# Display.net
KiCad netlist of a schematic drawn in Altium Designer
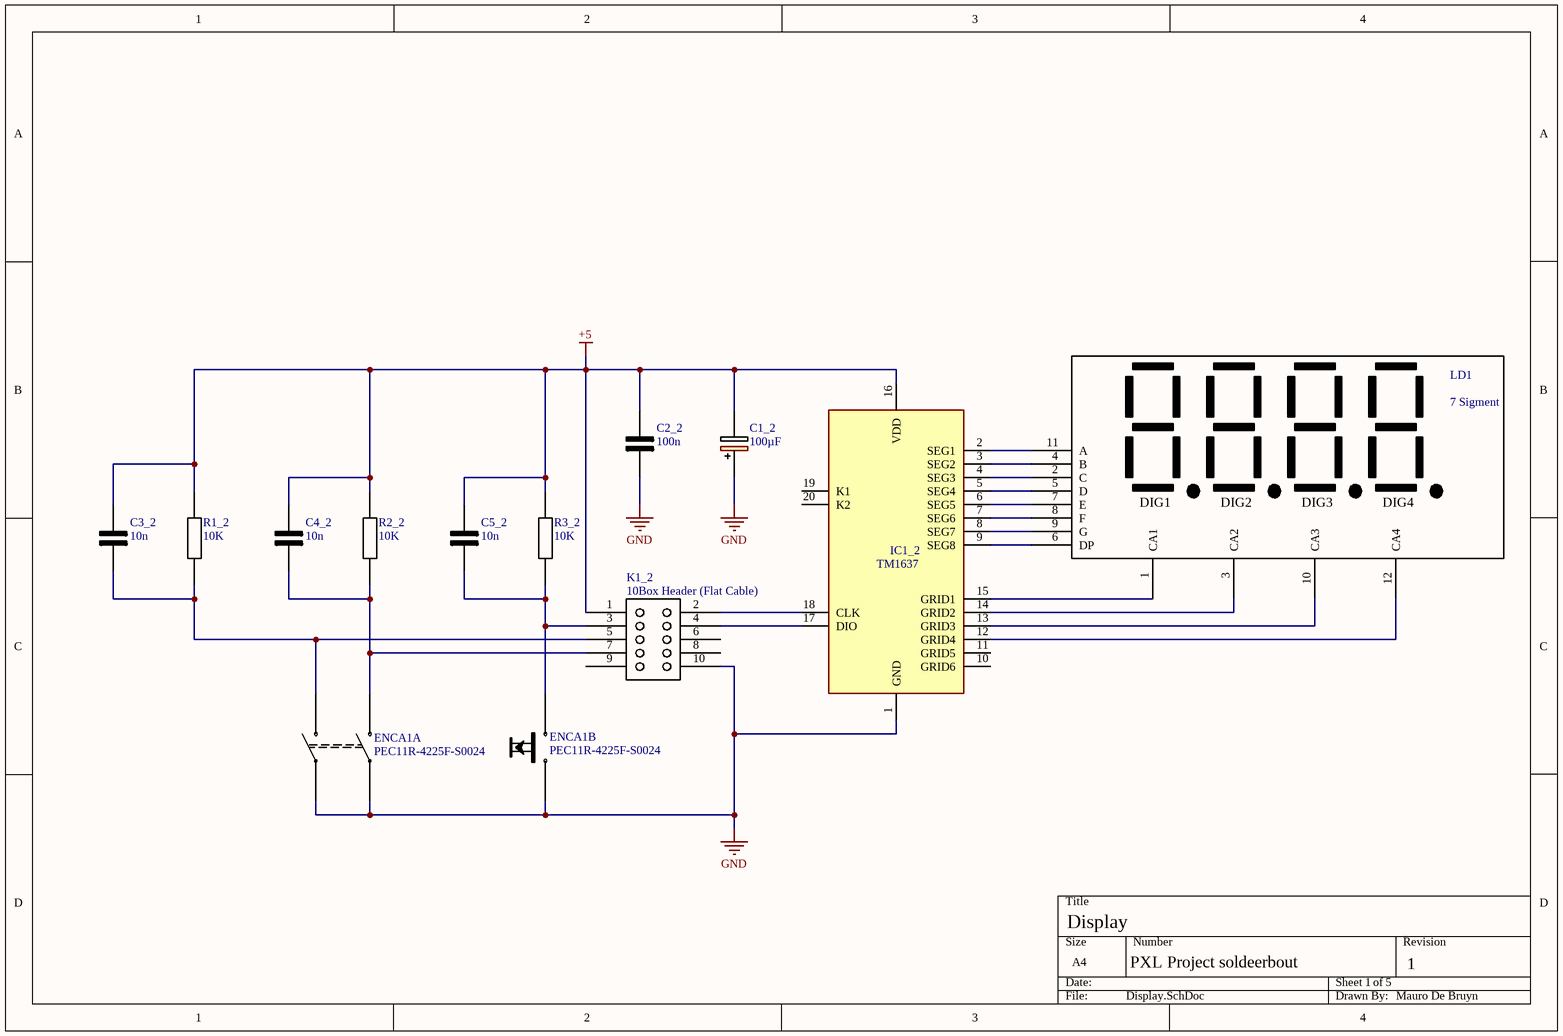
[diagram p0: Display.SchDoc]

(export (version "E")
  (design (tool "Eeschema 10.0.6"))
  (components
    (comp (ref "C1_2")
      (value "100µF")
      (footprint "SamacSys:CAPPRD350W60D825H1300")
      (description "Capacitor Polarised")
      (fields (field (name "MANUFACTURER_PART_NUMBER") "RGA101M1HBK-0811G"))
      (libsource (lib "SamacSys") (part "RGA101M1HBK-0811G"))
    )
    (comp (ref "C2_2")
      (value "100n")
      (footprint "SamacSys:C0805")
      (description "Capacitor")
      (fields (field (name "MANUFACTURER_PART_NUMBER") "C0805C391G3GACTU"))
      (libsource (lib "SamacSys") (part "0805_1"))
    )
    (comp (ref "C3_2")
      (value "10n")
      (footprint "SamacSys:C0805")
      (description "Capacitor")
      (fields (field (name "MANUFACTURER_PART_NUMBER") "C0805C391G3GACTU"))
      (libsource (lib "SamacSys") (part "0805_1"))
    )
    (comp (ref "C4_2")
      (value "10n")
      (footprint "SamacSys:C0805")
      (description "Capacitor")
      (fields (field (name "MANUFACTURER_PART_NUMBER") "C0805C391G3GACTU"))
      (libsource (lib "SamacSys") (part "0805_1"))
    )
    (comp (ref "C5_2")
      (value "10n")
      (footprint "SamacSys:C0805")
      (description "Capacitor")
      (fields (field (name "MANUFACTURER_PART_NUMBER") "C0805C391G3GACTU"))
      (libsource (lib "SamacSys") (part "0805_1"))
    )
    (comp (ref "ENCA1")
      (value "PEC11R-4225F-S0024")
      (footprint "SamacSys:PEC12R-4XXXF-SXXXX_1")
      (description "Undefined or Miscellaneous")
      (fields (field (name "MOUSER2 PART NUMBER") "652-PEC11R-4225F-S24"))
      (libsource (lib "SamacSys") (part "PEC11R-4225F-S0024"))
    )
    (comp (ref "IC1_2")
      (value "TM1637")
      (footprint "SamacSys:tm1637")
      (description "Integrated Circuit")
      (fields (field (name "MANUFACTURER_PART_NUMBER") "TM1637 (SOP)"))
      (libsource (lib "SamacSys") (part "TM1637__SOP_"))
    )
    (comp (ref "K1_2")
      (value "10Box Header (Flat Cable)")
      (footprint "SamacSys:10BoxHeader")
      (libsource (lib "SamacSys") (part "10Box Header (Flat Cable)"))
    )
    (comp (ref "LD1")
      (value "7 Sigment")
      (footprint "SamacSys:7-Sigment")
      (libsource (lib "SamacSys") (part "7 Sigment"))
    )
    (comp (ref "R1_2")
      (value "10K")
      (footprint "SamacSys:C0805")
      (description "Resistor")
      (fields (field (name "MANUFACTURER_PART_NUMBER") "C0805C391G3GACTU"))
      (libsource (lib "SamacSys") (part "0805"))
    )
    (comp (ref "R2_2")
      (value "10K")
      (footprint "SamacSys:C0805")
      (description "Resistor")
      (fields (field (name "MANUFACTURER_PART_NUMBER") "C0805C391G3GACTU"))
      (libsource (lib "SamacSys") (part "0805"))
    )
    (comp (ref "R3_2")
      (value "10K")
      (footprint "SamacSys:C0805")
      (description "Resistor")
      (fields (field (name "MANUFACTURER_PART_NUMBER") "C0805C391G3GACTU"))
      (libsource (lib "SamacSys") (part "0805"))
    )
  )
  (nets
    (net (code "1") (name "+5") (class "Default")
      (node (ref "C1_2") (pin "2") (pinfunction "-_2") (pintype "passive"))
      (node (ref "C2_2") (pin "2") (pinfunction "-_2") (pintype "passive"))
      (node (ref "C3_2") (pin "2") (pinfunction "-_2") (pintype "passive"))
      (node (ref "C4_2") (pin "2") (pinfunction "-_2") (pintype "passive"))
      (node (ref "C5_2") (pin "2") (pinfunction "-_2") (pintype "passive"))
      (node (ref "IC1_2") (pin "16") (pinfunction "VDD_16") (pintype "passive"))
      (node (ref "K1_2") (pin "1") (pinfunction "1_1") (pintype "passive"))
      (node (ref "R1_2") (pin "2") (pinfunction "2_2") (pintype "passive"))
      (node (ref "R2_2") (pin "2") (pinfunction "2_2") (pintype "passive"))
      (node (ref "R3_2") (pin "2") (pinfunction "2_2") (pintype "passive"))
    )
    (net (code "2") (name "GND") (class "Default")
      (node (ref "C1_2") (pin "1") (pinfunction "+_1") (pintype "passive"))
      (node (ref "C2_2") (pin "1") (pinfunction "+_1") (pintype "passive"))
      (node (ref "ENCA1") (pin "2") (pinfunction "2_2") (pintype "passive"))
      (node (ref "ENCA1") (pin "4") (pinfunction "4_4") (pintype "passive"))
      (node (ref "ENCA1") (pin "6") (pinfunction "6_6") (pintype "passive"))
      (node (ref "IC1_2") (pin "1") (pinfunction "GND_1") (pintype "passive"))
      (node (ref "K1_2") (pin "10") (pinfunction "10_10") (pintype "passive"))
    )
    (net (code "3") (name "Net-(C3_2-+)") (class "Default")
      (node (ref "C3_2") (pin "1") (pinfunction "+_1") (pintype "passive"))
      (node (ref "ENCA1") (pin "1") (pinfunction "1_1") (pintype "passive"))
      (node (ref "K1_2") (pin "5") (pinfunction "5_5") (pintype "passive"))
      (node (ref "R1_2") (pin "1") (pinfunction "1_1") (pintype "passive"))
    )
    (net (code "4") (name "Net-(C4_2-+)") (class "Default")
      (node (ref "C4_2") (pin "1") (pinfunction "+_1") (pintype "passive"))
      (node (ref "ENCA1") (pin "3") (pinfunction "3_3") (pintype "passive"))
      (node (ref "K1_2") (pin "7") (pinfunction "7_7") (pintype "passive"))
      (node (ref "R2_2") (pin "1") (pinfunction "1_1") (pintype "passive"))
    )
    (net (code "5") (name "Net-(C5_2-+)") (class "Default")
      (node (ref "C5_2") (pin "1") (pinfunction "+_1") (pintype "passive"))
      (node (ref "ENCA1") (pin "5") (pinfunction "5_5") (pintype "passive"))
      (node (ref "K1_2") (pin "3") (pinfunction "3_3") (pintype "passive"))
      (node (ref "R3_2") (pin "1") (pinfunction "1_1") (pintype "passive"))
    )
    (net (code "6") (name "Net-(IC1_2-CLK)") (class "Default")
      (node (ref "IC1_2") (pin "18") (pinfunction "CLK_18") (pintype "passive"))
      (node (ref "K1_2") (pin "2") (pinfunction "2_2") (pintype "passive"))
    )
    (net (code "7") (name "Net-(IC1_2-DIO)") (class "Default")
      (node (ref "IC1_2") (pin "17") (pinfunction "DIO_17") (pintype "passive"))
      (node (ref "K1_2") (pin "4") (pinfunction "4_4") (pintype "passive"))
    )
    (net (code "8") (name "Net-(IC1_2-GRID1)") (class "Default")
      (node (ref "IC1_2") (pin "15") (pinfunction "GRID1_15") (pintype "passive"))
      (node (ref "LD1") (pin "1") (pinfunction "CA1_1") (pintype "passive"))
    )
    (net (code "9") (name "Net-(IC1_2-GRID2)") (class "Default")
      (node (ref "IC1_2") (pin "14") (pinfunction "GRID2_14") (pintype "passive"))
      (node (ref "LD1") (pin "3") (pinfunction "CA2_3") (pintype "passive"))
    )
    (net (code "10") (name "Net-(IC1_2-GRID3)") (class "Default")
      (node (ref "IC1_2") (pin "13") (pinfunction "GRID3_13") (pintype "passive"))
      (node (ref "LD1") (pin "10") (pinfunction "CA3_10") (pintype "passive"))
    )
    (net (code "11") (name "Net-(IC1_2-GRID4)") (class "Default")
      (node (ref "IC1_2") (pin "12") (pinfunction "GRID4_12") (pintype "passive"))
      (node (ref "LD1") (pin "12") (pinfunction "CA4_12") (pintype "passive"))
    )
    (net (code "12") (name "Net-(IC1_2-SEG1)") (class "Default")
      (node (ref "IC1_2") (pin "2") (pinfunction "SEG1_2") (pintype "passive"))
      (node (ref "LD1") (pin "11") (pinfunction "A_11") (pintype "passive"))
    )
    (net (code "13") (name "Net-(IC1_2-SEG2)") (class "Default")
      (node (ref "IC1_2") (pin "3") (pinfunction "SEG2_3") (pintype "passive"))
      (node (ref "LD1") (pin "4") (pinfunction "B_4") (pintype "passive"))
    )
    (net (code "14") (name "Net-(IC1_2-SEG3)") (class "Default")
      (node (ref "IC1_2") (pin "4") (pinfunction "SEG3_4") (pintype "passive"))
      (node (ref "LD1") (pin "2") (pinfunction "C_2") (pintype "passive"))
    )
    (net (code "15") (name "Net-(IC1_2-SEG4)") (class "Default")
      (node (ref "IC1_2") (pin "5") (pinfunction "SEG4_5") (pintype "passive"))
      (node (ref "LD1") (pin "5") (pinfunction "D_5") (pintype "passive"))
    )
    (net (code "16") (name "Net-(IC1_2-SEG5)") (class "Default")
      (node (ref "IC1_2") (pin "6") (pinfunction "SEG5_6") (pintype "passive"))
      (node (ref "LD1") (pin "7") (pinfunction "E_7") (pintype "passive"))
    )
    (net (code "17") (name "Net-(IC1_2-SEG6)") (class "Default")
      (node (ref "IC1_2") (pin "7") (pinfunction "SEG6_7") (pintype "passive"))
      (node (ref "LD1") (pin "8") (pinfunction "F_8") (pintype "passive"))
    )
    (net (code "18") (name "Net-(IC1_2-SEG7)") (class "Default")
      (node (ref "IC1_2") (pin "8") (pinfunction "SEG7_8") (pintype "passive"))
      (node (ref "LD1") (pin "9") (pinfunction "G_9") (pintype "passive"))
    )
    (net (code "19") (name "Net-(IC1_2-SEG8)") (class "Default")
      (node (ref "IC1_2") (pin "9") (pinfunction "SEG8_9") (pintype "passive"))
      (node (ref "LD1") (pin "6") (pinfunction "DP_6") (pintype "passive"))
    )
    (net (code "20") (name "unconnected-(IC1_2-GRID5-Pad11)") (class "Default")
      (node (ref "IC1_2") (pin "11") (pinfunction "GRID5_11") (pintype "passive"))
    )
    (net (code "21") (name "unconnected-(IC1_2-GRID6-Pad10)") (class "Default")
      (node (ref "IC1_2") (pin "10") (pinfunction "GRID6_10") (pintype "passive"))
    )
    (net (code "22") (name "unconnected-(IC1_2-K1-Pad19)") (class "Default")
      (node (ref "IC1_2") (pin "19") (pinfunction "K1_19") (pintype "passive"))
    )
    (net (code "23") (name "unconnected-(IC1_2-K2-Pad20)") (class "Default")
      (node (ref "IC1_2") (pin "20") (pinfunction "K2_20") (pintype "passive"))
    )
    (net (code "24") (name "unconnected-(K1_2-Pad6)") (class "Default")
      (node (ref "K1_2") (pin "6") (pinfunction "6_6") (pintype "passive"))
    )
    (net (code "25") (name "unconnected-(K1_2-Pad8)") (class "Default")
      (node (ref "K1_2") (pin "8") (pinfunction "8_8") (pintype "passive"))
    )
    (net (code "26") (name "unconnected-(K1_2-Pad9)") (class "Default")
      (node (ref "K1_2") (pin "9") (pinfunction "9_9") (pintype "passive"))
    )
  )
)
